# Controller2019.net
KiCad netlist of a schematic drawn in EAGLE
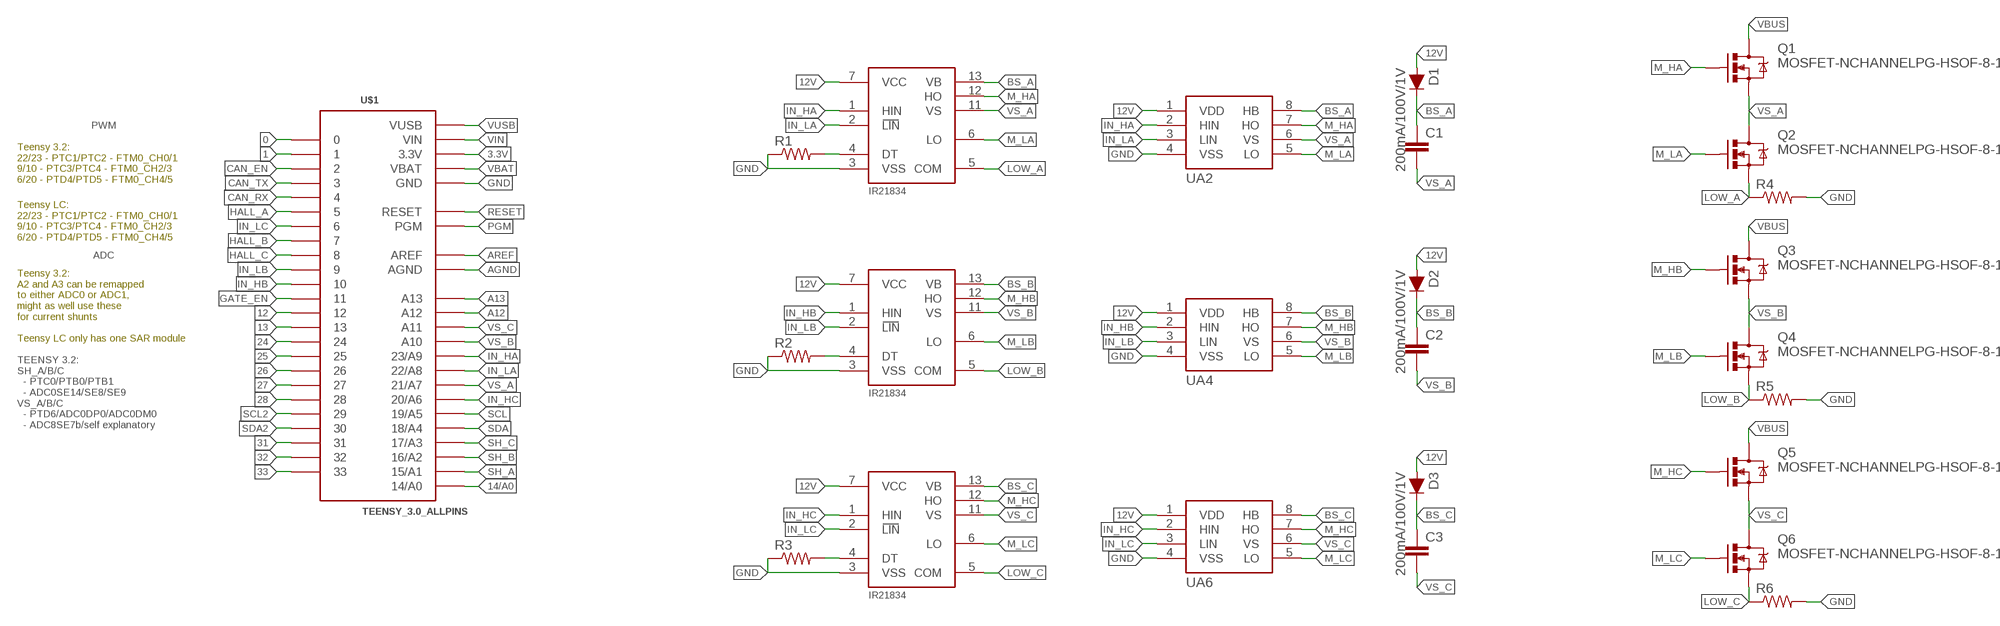
[diagram p0: schematic, sheet 1]

(export (version "E")
  (design (tool "Eeschema 10.0.6"))
  (components
    (comp (ref "C1")
      (value "CAP0603-CAP")
      (footprint "eagle-import:0603-CAP")
      (libsource (lib "eagle-import") (part "CAP0603-CAP"))
    )
    (comp (ref "C2")
      (value "CAP0603-CAP")
      (footprint "eagle-import:0603-CAP")
      (libsource (lib "eagle-import") (part "CAP0603-CAP"))
    )
    (comp (ref "C3")
      (value "CAP0603-CAP")
      (footprint "eagle-import:0603-CAP")
      (libsource (lib "eagle-import") (part "CAP0603-CAP"))
    )
    (comp (ref "D1")
      (value "200mA/100V/1V")
      (footprint "eagle-import:DIODE-1N4148")
      (libsource (lib "eagle-import") (part "DIODE-1N4148"))
    )
    (comp (ref "D2")
      (value "200mA/100V/1V")
      (footprint "eagle-import:DIODE-1N4148")
      (libsource (lib "eagle-import") (part "DIODE-1N4148"))
    )
    (comp (ref "D3")
      (value "200mA/100V/1V")
      (footprint "eagle-import:DIODE-1N4148")
      (libsource (lib "eagle-import") (part "DIODE-1N4148"))
    )
    (comp (ref "Q1")
      (value "MOSFET-NCHANNELPG-HSOF-8-1")
      (footprint "eagle-import:PG-HSOF-8-1")
      (libsource (lib "eagle-import") (part "MOSFET-NCHANNELPG-HSOF-8-1"))
    )
    (comp (ref "Q2")
      (value "MOSFET-NCHANNELPG-HSOF-8-1")
      (footprint "eagle-import:PG-HSOF-8-1")
      (libsource (lib "eagle-import") (part "MOSFET-NCHANNELPG-HSOF-8-1"))
    )
    (comp (ref "Q3")
      (value "MOSFET-NCHANNELPG-HSOF-8-1")
      (footprint "eagle-import:PG-HSOF-8-1")
      (libsource (lib "eagle-import") (part "MOSFET-NCHANNELPG-HSOF-8-1"))
    )
    (comp (ref "Q4")
      (value "MOSFET-NCHANNELPG-HSOF-8-1")
      (footprint "eagle-import:PG-HSOF-8-1")
      (libsource (lib "eagle-import") (part "MOSFET-NCHANNELPG-HSOF-8-1"))
    )
    (comp (ref "Q5")
      (value "MOSFET-NCHANNELPG-HSOF-8-1")
      (footprint "eagle-import:PG-HSOF-8-1")
      (libsource (lib "eagle-import") (part "MOSFET-NCHANNELPG-HSOF-8-1"))
    )
    (comp (ref "Q6")
      (value "MOSFET-NCHANNELPG-HSOF-8-1")
      (footprint "eagle-import:PG-HSOF-8-1")
      (libsource (lib "eagle-import") (part "MOSFET-NCHANNELPG-HSOF-8-1"))
    )
    (comp (ref "R1")
      (value "RESISTOR0603-RES")
      (footprint "eagle-import:0603-RES")
      (libsource (lib "eagle-import") (part "RESISTOR0603-RES"))
    )
    (comp (ref "R2")
      (value "RESISTOR0603-RES")
      (footprint "eagle-import:0603-RES")
      (libsource (lib "eagle-import") (part "RESISTOR0603-RES"))
    )
    (comp (ref "R3")
      (value "RESISTOR0603-RES")
      (footprint "eagle-import:0603-RES")
      (libsource (lib "eagle-import") (part "RESISTOR0603-RES"))
    )
    (comp (ref "R4")
      (value "RESISTOR2512")
      (footprint "eagle-import:R2512")
      (libsource (lib "eagle-import") (part "RESISTOR2512"))
    )
    (comp (ref "R5")
      (value "RESISTOR2512")
      (footprint "eagle-import:R2512")
      (libsource (lib "eagle-import") (part "RESISTOR2512"))
    )
    (comp (ref "R6")
      (value "RESISTOR2512")
      (footprint "eagle-import:R2512")
      (libsource (lib "eagle-import") (part "RESISTOR2512"))
    )
    (comp (ref "U$1")
      (value "TEENSY_3.0_ALLPINS")
      (footprint "eagle-import:TEENSY_3.0_ALLPINS")
      (libsource (lib "eagle-import") (part "TEENSY_3.0_ALLPINS"))
    )
    (comp (ref "UA1")
      (value "IR21834")
      (footprint "eagle-import:SO14")
      (libsource (lib "eagle-import") (part "IR21834"))
    )
    (comp (ref "UA2")
      (value "GATEDRIVER_IND_ISL6700")
      (footprint "eagle-import:SOIC8")
      (libsource (lib "eagle-import") (part "GATEDRIVER_IND_ISL6700"))
    )
    (comp (ref "UA3")
      (value "IR21834")
      (footprint "eagle-import:SO14")
      (libsource (lib "eagle-import") (part "IR21834"))
    )
    (comp (ref "UA4")
      (value "GATEDRIVER_IND_ISL6700")
      (footprint "eagle-import:SOIC8")
      (libsource (lib "eagle-import") (part "GATEDRIVER_IND_ISL6700"))
    )
    (comp (ref "UA5")
      (value "IR21834")
      (footprint "eagle-import:SO14")
      (libsource (lib "eagle-import") (part "IR21834"))
    )
    (comp (ref "UA6")
      (value "GATEDRIVER_IND_ISL6700")
      (footprint "eagle-import:SOIC8")
      (libsource (lib "eagle-import") (part "GATEDRIVER_IND_ISL6700"))
    )
  )
  (nets
    (net (code "1") (name "0") (class "Default")
      (node (ref "U$1") (pin "0") (pinfunction "0_0") (pintype "bidirectional"))
    )
    (net (code "2") (name "1") (class "Default")
      (node (ref "U$1") (pin "1") (pinfunction "1_1") (pintype "bidirectional"))
    )
    (net (code "3") (name "3.3V") (class "Default")
      (node (ref "U$1") (pin "3.3V") (pinfunction "3.3V_3.3V") (pintype "power_in"))
      (node (ref "U$1") (pin "3.3V1") (pinfunction "3.3V_3.3V1") (pintype "power_in"))
      (node (ref "U$1") (pin "3.3V2") (pinfunction "3.3V_3.3V2") (pintype "power_in"))
    )
    (net (code "4") (name "12") (class "Default")
      (node (ref "U$1") (pin "12") (pinfunction "12_12") (pintype "bidirectional"))
    )
    (net (code "5") (name "12V") (class "Default")
      (node (ref "D1") (pin "A") (pinfunction "A_A") (pintype "passive"))
      (node (ref "D2") (pin "A") (pinfunction "A_A") (pintype "passive"))
      (node (ref "D3") (pin "A") (pinfunction "A_A") (pintype "passive"))
      (node (ref "UA1") (pin "7") (pinfunction "VCC_7") (pintype "bidirectional"))
      (node (ref "UA2") (pin "1") (pinfunction "VDD_1") (pintype "bidirectional"))
      (node (ref "UA3") (pin "7") (pinfunction "VCC_7") (pintype "bidirectional"))
      (node (ref "UA4") (pin "1") (pinfunction "VDD_1") (pintype "bidirectional"))
      (node (ref "UA5") (pin "7") (pinfunction "VCC_7") (pintype "bidirectional"))
      (node (ref "UA6") (pin "1") (pinfunction "VDD_1") (pintype "bidirectional"))
    )
    (net (code "6") (name "13") (class "Default")
      (node (ref "U$1") (pin "13") (pinfunction "13_13") (pintype "bidirectional"))
    )
    (net (code "7") (name "14{slash}A0") (class "Default")
      (node (ref "U$1") (pin "14/A0") (pinfunction "14/A0_14/A0") (pintype "bidirectional"))
    )
    (net (code "8") (name "24") (class "Default")
      (node (ref "U$1") (pin "24") (pinfunction "24_24") (pintype "bidirectional"))
    )
    (net (code "9") (name "25") (class "Default")
      (node (ref "U$1") (pin "25") (pinfunction "25_25") (pintype "bidirectional"))
    )
    (net (code "10") (name "26") (class "Default")
      (node (ref "U$1") (pin "26") (pinfunction "26_26") (pintype "bidirectional"))
    )
    (net (code "11") (name "27") (class "Default")
      (node (ref "U$1") (pin "27") (pinfunction "27_27") (pintype "bidirectional"))
    )
    (net (code "12") (name "28") (class "Default")
      (node (ref "U$1") (pin "28") (pinfunction "28_28") (pintype "bidirectional"))
    )
    (net (code "13") (name "31") (class "Default")
      (node (ref "U$1") (pin "31") (pinfunction "31_31") (pintype "bidirectional"))
    )
    (net (code "14") (name "32") (class "Default")
      (node (ref "U$1") (pin "32") (pinfunction "32_32") (pintype "bidirectional"))
    )
    (net (code "15") (name "33") (class "Default")
      (node (ref "U$1") (pin "33") (pinfunction "33_33") (pintype "bidirectional"))
    )
    (net (code "16") (name "A12") (class "Default")
      (node (ref "U$1") (pin "A12") (pinfunction "A12_A12") (pintype "bidirectional"))
    )
    (net (code "17") (name "A13") (class "Default")
      (node (ref "U$1") (pin "A13") (pinfunction "A13_A13") (pintype "bidirectional"))
    )
    (net (code "18") (name "AGND") (class "Default")
      (node (ref "U$1") (pin "AGND") (pinfunction "AGND_AGND") (pintype "power_in"))
    )
    (net (code "19") (name "AREF") (class "Default")
      (node (ref "U$1") (pin "AREF") (pinfunction "AREF_AREF") (pintype "power_in"))
    )
    (net (code "20") (name "BS_A") (class "Default")
      (node (ref "C1") (pin "1") (pinfunction "1_1") (pintype "passive"))
      (node (ref "D1") (pin "C") (pinfunction "C_C") (pintype "passive"))
      (node (ref "UA1") (pin "13") (pinfunction "VB_13") (pintype "bidirectional"))
      (node (ref "UA2") (pin "8") (pinfunction "HB_8") (pintype "bidirectional"))
    )
    (net (code "21") (name "BS_B") (class "Default")
      (node (ref "C2") (pin "1") (pinfunction "1_1") (pintype "passive"))
      (node (ref "D2") (pin "C") (pinfunction "C_C") (pintype "passive"))
      (node (ref "UA3") (pin "13") (pinfunction "VB_13") (pintype "bidirectional"))
      (node (ref "UA4") (pin "8") (pinfunction "HB_8") (pintype "bidirectional"))
    )
    (net (code "22") (name "BS_C") (class "Default")
      (node (ref "C3") (pin "1") (pinfunction "1_1") (pintype "passive"))
      (node (ref "D3") (pin "C") (pinfunction "C_C") (pintype "passive"))
      (node (ref "UA5") (pin "13") (pinfunction "VB_13") (pintype "bidirectional"))
      (node (ref "UA6") (pin "8") (pinfunction "HB_8") (pintype "bidirectional"))
    )
    (net (code "23") (name "CAN_EN") (class "Default")
      (node (ref "U$1") (pin "2") (pinfunction "2_2") (pintype "bidirectional"))
    )
    (net (code "24") (name "CAN_RX") (class "Default")
      (node (ref "U$1") (pin "4") (pinfunction "4_4") (pintype "bidirectional"))
    )
    (net (code "25") (name "CAN_TX") (class "Default")
      (node (ref "U$1") (pin "3") (pinfunction "3_3") (pintype "bidirectional"))
    )
    (net (code "26") (name "GATE_EN") (class "Default")
      (node (ref "U$1") (pin "11") (pinfunction "11_11") (pintype "bidirectional"))
    )
    (net (code "27") (name "GND") (class "Default")
      (node (ref "R1") (pin "1") (pinfunction "1_1") (pintype "passive"))
      (node (ref "R2") (pin "1") (pinfunction "1_1") (pintype "passive"))
      (node (ref "R3") (pin "1") (pinfunction "1_1") (pintype "passive"))
      (node (ref "R4") (pin "2") (pinfunction "2_2") (pintype "passive"))
      (node (ref "R5") (pin "2") (pinfunction "2_2") (pintype "passive"))
      (node (ref "R6") (pin "2") (pinfunction "2_2") (pintype "passive"))
      (node (ref "U$1") (pin "GND") (pinfunction "GND_GND") (pintype "power_in"))
      (node (ref "U$1") (pin "GND1") (pinfunction "GND_GND1") (pintype "power_in"))
      (node (ref "U$1") (pin "GND2") (pinfunction "GND_GND2") (pintype "power_in"))
      (node (ref "UA1") (pin "3") (pinfunction "VSS_3") (pintype "bidirectional"))
      (node (ref "UA2") (pin "4") (pinfunction "VSS_4") (pintype "bidirectional"))
      (node (ref "UA3") (pin "3") (pinfunction "VSS_3") (pintype "bidirectional"))
      (node (ref "UA4") (pin "4") (pinfunction "VSS_4") (pintype "bidirectional"))
      (node (ref "UA5") (pin "3") (pinfunction "VSS_3") (pintype "bidirectional"))
      (node (ref "UA6") (pin "4") (pinfunction "VSS_4") (pintype "bidirectional"))
    )
    (net (code "28") (name "HALL_A") (class "Default")
      (node (ref "U$1") (pin "5") (pinfunction "5_5") (pintype "bidirectional"))
    )
    (net (code "29") (name "HALL_B") (class "Default")
      (node (ref "U$1") (pin "7") (pinfunction "7_7") (pintype "bidirectional"))
    )
    (net (code "30") (name "HALL_C") (class "Default")
      (node (ref "U$1") (pin "8") (pinfunction "8_8") (pintype "bidirectional"))
    )
    (net (code "31") (name "IN_HA") (class "Default")
      (node (ref "U$1") (pin "23/A9") (pinfunction "23/A9_23/A9") (pintype "bidirectional"))
      (node (ref "UA1") (pin "1") (pinfunction "HIN_1") (pintype "bidirectional"))
      (node (ref "UA2") (pin "2") (pinfunction "HIN_2") (pintype "bidirectional"))
    )
    (net (code "32") (name "IN_HB") (class "Default")
      (node (ref "U$1") (pin "10") (pinfunction "10_10") (pintype "bidirectional"))
      (node (ref "UA3") (pin "1") (pinfunction "HIN_1") (pintype "bidirectional"))
      (node (ref "UA4") (pin "2") (pinfunction "HIN_2") (pintype "bidirectional"))
    )
    (net (code "33") (name "IN_HC") (class "Default")
      (node (ref "U$1") (pin "20/A6") (pinfunction "20/A6_20/A6") (pintype "bidirectional"))
      (node (ref "UA5") (pin "1") (pinfunction "HIN_1") (pintype "bidirectional"))
      (node (ref "UA6") (pin "2") (pinfunction "HIN_2") (pintype "bidirectional"))
    )
    (net (code "34") (name "IN_LA") (class "Default")
      (node (ref "U$1") (pin "22/A8") (pinfunction "22/A8_22/A8") (pintype "bidirectional"))
      (node (ref "UA1") (pin "2") (pinfunction "LIN_2") (pintype "bidirectional"))
      (node (ref "UA2") (pin "3") (pinfunction "LIN_3") (pintype "bidirectional"))
    )
    (net (code "35") (name "IN_LB") (class "Default")
      (node (ref "U$1") (pin "9") (pinfunction "9_9") (pintype "bidirectional"))
      (node (ref "UA3") (pin "2") (pinfunction "LIN_2") (pintype "bidirectional"))
      (node (ref "UA4") (pin "3") (pinfunction "LIN_3") (pintype "bidirectional"))
    )
    (net (code "36") (name "IN_LC") (class "Default")
      (node (ref "U$1") (pin "6") (pinfunction "6_6") (pintype "bidirectional"))
      (node (ref "UA5") (pin "2") (pinfunction "LIN_2") (pintype "bidirectional"))
      (node (ref "UA6") (pin "3") (pinfunction "LIN_3") (pintype "bidirectional"))
    )
    (net (code "37") (name "LOW_A") (class "Default")
      (node (ref "Q2") (pin "S") (pinfunction "S_S") (pintype "passive"))
      (node (ref "R4") (pin "1") (pinfunction "1_1") (pintype "passive"))
      (node (ref "UA1") (pin "5") (pinfunction "COM_5") (pintype "bidirectional"))
    )
    (net (code "38") (name "LOW_B") (class "Default")
      (node (ref "Q4") (pin "S") (pinfunction "S_S") (pintype "passive"))
      (node (ref "R5") (pin "1") (pinfunction "1_1") (pintype "passive"))
      (node (ref "UA3") (pin "5") (pinfunction "COM_5") (pintype "bidirectional"))
    )
    (net (code "39") (name "LOW_C") (class "Default")
      (node (ref "Q6") (pin "S") (pinfunction "S_S") (pintype "passive"))
      (node (ref "R6") (pin "1") (pinfunction "1_1") (pintype "passive"))
      (node (ref "UA5") (pin "5") (pinfunction "COM_5") (pintype "bidirectional"))
    )
    (net (code "40") (name "M_HA") (class "Default")
      (node (ref "Q1") (pin "G") (pinfunction "G_G") (pintype "passive"))
      (node (ref "UA1") (pin "12") (pinfunction "HO_12") (pintype "bidirectional"))
      (node (ref "UA2") (pin "7") (pinfunction "HO_7") (pintype "bidirectional"))
    )
    (net (code "41") (name "M_HB") (class "Default")
      (node (ref "Q3") (pin "G") (pinfunction "G_G") (pintype "passive"))
      (node (ref "UA3") (pin "12") (pinfunction "HO_12") (pintype "bidirectional"))
      (node (ref "UA4") (pin "7") (pinfunction "HO_7") (pintype "bidirectional"))
    )
    (net (code "42") (name "M_HC") (class "Default")
      (node (ref "Q5") (pin "G") (pinfunction "G_G") (pintype "passive"))
      (node (ref "UA5") (pin "12") (pinfunction "HO_12") (pintype "bidirectional"))
      (node (ref "UA6") (pin "7") (pinfunction "HO_7") (pintype "bidirectional"))
    )
    (net (code "43") (name "M_LA") (class "Default")
      (node (ref "Q2") (pin "G") (pinfunction "G_G") (pintype "passive"))
      (node (ref "UA1") (pin "6") (pinfunction "LO_6") (pintype "bidirectional"))
      (node (ref "UA2") (pin "5") (pinfunction "LO_5") (pintype "bidirectional"))
    )
    (net (code "44") (name "M_LB") (class "Default")
      (node (ref "Q4") (pin "G") (pinfunction "G_G") (pintype "passive"))
      (node (ref "UA3") (pin "6") (pinfunction "LO_6") (pintype "bidirectional"))
      (node (ref "UA4") (pin "5") (pinfunction "LO_5") (pintype "bidirectional"))
    )
    (net (code "45") (name "M_LC") (class "Default")
      (node (ref "Q6") (pin "G") (pinfunction "G_G") (pintype "passive"))
      (node (ref "UA5") (pin "6") (pinfunction "LO_6") (pintype "bidirectional"))
      (node (ref "UA6") (pin "5") (pinfunction "LO_5") (pintype "bidirectional"))
    )
    (net (code "46") (name "Net-(UA1-DT)") (class "Default")
      (node (ref "R1") (pin "2") (pinfunction "2_2") (pintype "passive"))
      (node (ref "UA1") (pin "4") (pinfunction "DT_4") (pintype "bidirectional"))
    )
    (net (code "47") (name "Net-(UA3-DT)") (class "Default")
      (node (ref "R2") (pin "2") (pinfunction "2_2") (pintype "passive"))
      (node (ref "UA3") (pin "4") (pinfunction "DT_4") (pintype "bidirectional"))
    )
    (net (code "48") (name "Net-(UA5-DT)") (class "Default")
      (node (ref "R3") (pin "2") (pinfunction "2_2") (pintype "passive"))
      (node (ref "UA5") (pin "4") (pinfunction "DT_4") (pintype "bidirectional"))
    )
    (net (code "49") (name "PGM") (class "Default")
      (node (ref "U$1") (pin "PGM") (pinfunction "PGM_PGM") (pintype "bidirectional"))
    )
    (net (code "50") (name "RESET") (class "Default")
      (node (ref "U$1") (pin "RESET") (pinfunction "RESET_RESET") (pintype "bidirectional"))
    )
    (net (code "51") (name "SCL") (class "Default")
      (node (ref "U$1") (pin "19/A5") (pinfunction "19/A5_19/A5") (pintype "bidirectional"))
    )
    (net (code "52") (name "SCL2") (class "Default")
      (node (ref "U$1") (pin "29") (pinfunction "29_29") (pintype "bidirectional"))
    )
    (net (code "53") (name "SDA") (class "Default")
      (node (ref "U$1") (pin "18/A4") (pinfunction "18/A4_18/A4") (pintype "bidirectional"))
    )
    (net (code "54") (name "SDA2") (class "Default")
      (node (ref "U$1") (pin "30") (pinfunction "30_30") (pintype "bidirectional"))
    )
    (net (code "55") (name "SH_A") (class "Default")
      (node (ref "U$1") (pin "15/A1") (pinfunction "15/A1_15/A1") (pintype "bidirectional"))
    )
    (net (code "56") (name "SH_B") (class "Default")
      (node (ref "U$1") (pin "16/A2") (pinfunction "16/A2_16/A2") (pintype "bidirectional"))
    )
    (net (code "57") (name "SH_C") (class "Default")
      (node (ref "U$1") (pin "17/A3") (pinfunction "17/A3_17/A3") (pintype "bidirectional"))
    )
    (net (code "58") (name "VBAT") (class "Default")
      (node (ref "U$1") (pin "VBAT") (pinfunction "VBAT_VBAT") (pintype "power_in"))
    )
    (net (code "59") (name "VBUS") (class "Default")
      (node (ref "Q1") (pin "D") (pinfunction "D_D") (pintype "passive"))
      (node (ref "Q3") (pin "D") (pinfunction "D_D") (pintype "passive"))
      (node (ref "Q5") (pin "D") (pinfunction "D_D") (pintype "passive"))
    )
    (net (code "60") (name "VIN") (class "Default")
      (node (ref "U$1") (pin "VIN") (pinfunction "VIN_VIN") (pintype "power_in"))
    )
    (net (code "61") (name "VS_A") (class "Default")
      (node (ref "C1") (pin "2") (pinfunction "2_2") (pintype "passive"))
      (node (ref "Q1") (pin "S") (pinfunction "S_S") (pintype "passive"))
      (node (ref "Q2") (pin "D") (pinfunction "D_D") (pintype "passive"))
      (node (ref "U$1") (pin "21/A7") (pinfunction "21/A7_21/A7") (pintype "bidirectional"))
      (node (ref "UA1") (pin "11") (pinfunction "VS_11") (pintype "bidirectional"))
      (node (ref "UA2") (pin "6") (pinfunction "VS_6") (pintype "bidirectional"))
    )
    (net (code "62") (name "VS_B") (class "Default")
      (node (ref "C2") (pin "2") (pinfunction "2_2") (pintype "passive"))
      (node (ref "Q3") (pin "S") (pinfunction "S_S") (pintype "passive"))
      (node (ref "Q4") (pin "D") (pinfunction "D_D") (pintype "passive"))
      (node (ref "U$1") (pin "A10") (pinfunction "A10_A10") (pintype "bidirectional"))
      (node (ref "UA3") (pin "11") (pinfunction "VS_11") (pintype "bidirectional"))
      (node (ref "UA4") (pin "6") (pinfunction "VS_6") (pintype "bidirectional"))
    )
    (net (code "63") (name "VS_C") (class "Default")
      (node (ref "C3") (pin "2") (pinfunction "2_2") (pintype "passive"))
      (node (ref "Q5") (pin "S") (pinfunction "S_S") (pintype "passive"))
      (node (ref "Q6") (pin "D") (pinfunction "D_D") (pintype "passive"))
      (node (ref "U$1") (pin "A11") (pinfunction "A11_A11") (pintype "bidirectional"))
      (node (ref "UA5") (pin "11") (pinfunction "VS_11") (pintype "bidirectional"))
      (node (ref "UA6") (pin "6") (pinfunction "VS_6") (pintype "bidirectional"))
    )
    (net (code "64") (name "VUSB") (class "Default")
      (node (ref "U$1") (pin "VUSB") (pinfunction "VUSB_VUSB") (pintype "power_in"))
    )
  )
)
